# week7-small.net
KiCad netlist of a schematic drawn in EAGLE
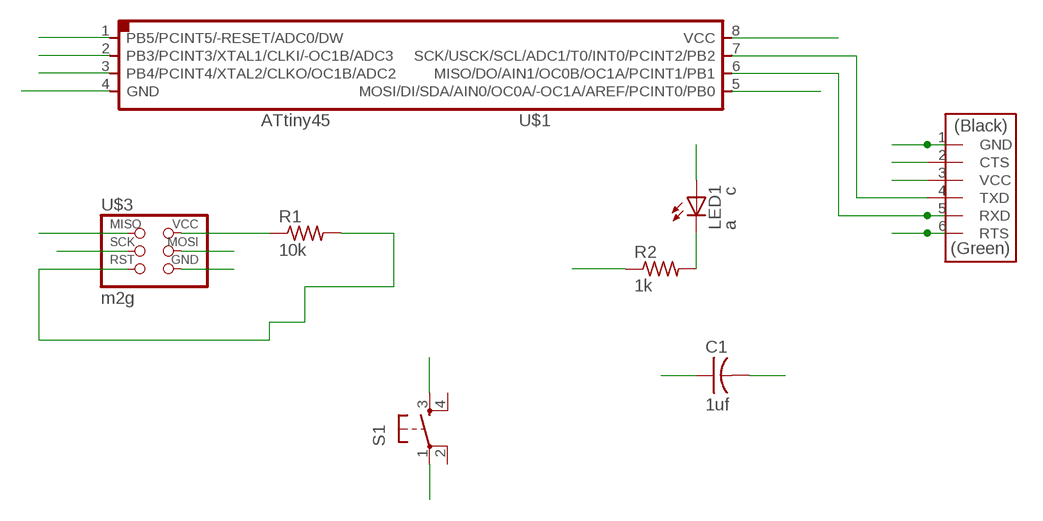
[diagram p0: schematic, sheet 1]

(export (version "E")
  (design (tool "Eeschema 10.0.6"))
  (components
    (comp (ref "C1")
      (value "1uf")
      (footprint "eagle-import:C1206FAB")
      (libsource (lib "eagle-import") (part "CAP-US1206FAB"))
    )
    (comp (ref "LED1")
      (value "a c")
      (footprint "eagle-import:LED1206FAB")
      (libsource (lib "eagle-import") (part "LEDFAB1206"))
    )
    (comp (ref "R1")
      (value "10k")
      (footprint "eagle-import:R1206FAB")
      (libsource (lib "eagle-import") (part "RES-US1206FAB"))
    )
    (comp (ref "R2")
      (value "1k")
      (footprint "eagle-import:R1206FAB")
      (libsource (lib "eagle-import") (part "RES-US1206FAB"))
    )
    (comp (ref "S1")
      (value "6MM_SWITCH6MM_SWITCH")
      (footprint "eagle-import:6MM_SWITCH")
      (libsource (lib "eagle-import") (part "6MM_SWITCH6MM_SWITCH"))
    )
    (comp (ref "U$1")
      (value "tt45")
      (footprint "eagle-import:SOIC8")
      (libsource (lib "eagle-import") (part "ATTINY45SI"))
    )
    (comp (ref "U$3")
      (value "m2g")
      (footprint "eagle-import:2X03SMD")
      (libsource (lib "eagle-import") (part "AVRISPSMD"))
    )
    (comp (ref "U$4")
      (value "FTDI-SMD-HEADER")
      (footprint "eagle-import:1X06SMD")
      (libsource (lib "eagle-import") (part "FTDI-SMD-HEADER"))
    )
  )
  (nets
    (net (code "1") (name "/GND") (class "Default")
      (node (ref "C1") (pin "2") (pinfunction "2_2") (pintype "passive"))
      (node (ref "R2") (pin "1") (pinfunction "1_1") (pintype "passive"))
      (node (ref "S1") (pin "3") (pinfunction "S_3") (pintype "passive"))
      (node (ref "U$1") (pin "4") (pinfunction "GND_4") (pintype "bidirectional"))
      (node (ref "U$3") (pin "6") (pinfunction "GND_6") (pintype "passive"))
      (node (ref "U$4") (pin "1") (pinfunction "GND_1") (pintype "bidirectional"))
    )
    (net (code "2") (name "/MISO") (class "Default")
      (node (ref "U$1") (pin "6") (pinfunction "MISO/DO/AIN1/OC0B/OC1A/PCINT1/PB1_6") (pintype "bidirectional"))
      (node (ref "U$3") (pin "1") (pinfunction "MISO_1") (pintype "passive"))
      (node (ref "U$4") (pin "5") (pinfunction "RXD_5") (pintype "bidirectional"))
    )
    (net (code "3") (name "/MOSI") (class "Default")
      (node (ref "U$1") (pin "5") (pinfunction "MOSI/DI/SDA/AIN0/OC0A/-OC1A/AREF/PCINT0/PB0_5") (pintype "bidirectional"))
      (node (ref "U$3") (pin "4") (pinfunction "MOSI_4") (pintype "passive"))
    )
    (net (code "4") (name "/RST") (class "Default")
      (node (ref "R1") (pin "2") (pinfunction "2_2") (pintype "passive"))
      (node (ref "U$1") (pin "1") (pinfunction "PB5/PCINT5/-RESET/ADC0/DW_1") (pintype "bidirectional"))
      (node (ref "U$3") (pin "5") (pinfunction "RST_5") (pintype "passive"))
    )
    (net (code "5") (name "/SCK") (class "Default")
      (node (ref "U$1") (pin "7") (pinfunction "SCK/USCK/SCL/ADC1/T0/INT0/PCINT2/PB2_7") (pintype "bidirectional"))
      (node (ref "U$3") (pin "3") (pinfunction "SCK_3") (pintype "passive"))
      (node (ref "U$4") (pin "4") (pinfunction "TXD_4") (pintype "bidirectional"))
    )
    (net (code "6") (name "/VCC") (class "Default")
      (node (ref "C1") (pin "1") (pinfunction "1_1") (pintype "passive"))
      (node (ref "R1") (pin "1") (pinfunction "1_1") (pintype "passive"))
      (node (ref "U$1") (pin "8") (pinfunction "VCC_8") (pintype "bidirectional"))
      (node (ref "U$3") (pin "2") (pinfunction "VCC_2") (pintype "passive"))
      (node (ref "U$4") (pin "3") (pinfunction "VCC_3") (pintype "bidirectional"))
    )
    (net (code "7") (name "/XTAL1") (class "Default")
      (node (ref "LED1") (pin "1") (pinfunction "A_1") (pintype "passive"))
      (node (ref "U$1") (pin "2") (pinfunction "PB3/PCINT3/XTAL1/CLKI/-OC1B/ADC3_2") (pintype "bidirectional"))
    )
    (net (code "8") (name "/XTAL2") (class "Default")
      (node (ref "S1") (pin "1") (pinfunction "P_1") (pintype "passive"))
      (node (ref "U$1") (pin "3") (pinfunction "PB4/PCINT4/XTAL2/CLKO/OC1B/ADC2_3") (pintype "bidirectional"))
    )
    (net (code "9") (name "Net-(LED1-C)") (class "Default")
      (node (ref "LED1") (pin "2") (pinfunction "C_2") (pintype "passive"))
      (node (ref "R2") (pin "2") (pinfunction "2_2") (pintype "passive"))
    )
    (net (code "10") (name "unconnected-(S1-P1-Pad2)") (class "Default")
      (node (ref "S1") (pin "2") (pinfunction "P1_2") (pintype "passive"))
    )
    (net (code "11") (name "unconnected-(S1-S1-Pad4)") (class "Default")
      (node (ref "S1") (pin "4") (pinfunction "S1_4") (pintype "passive"))
    )
    (net (code "12") (name "unconnected-(U$4-CTS-Pad2)") (class "Default")
      (node (ref "U$4") (pin "2") (pinfunction "CTS_2") (pintype "bidirectional"))
    )
    (net (code "13") (name "unconnected-(U$4-RTS-Pad6)") (class "Default")
      (node (ref "U$4") (pin "6") (pinfunction "RTS_6") (pintype "bidirectional"))
    )
  )
)
